# MB1166.net
KiCad netlist of a schematic drawn in Altium Designer
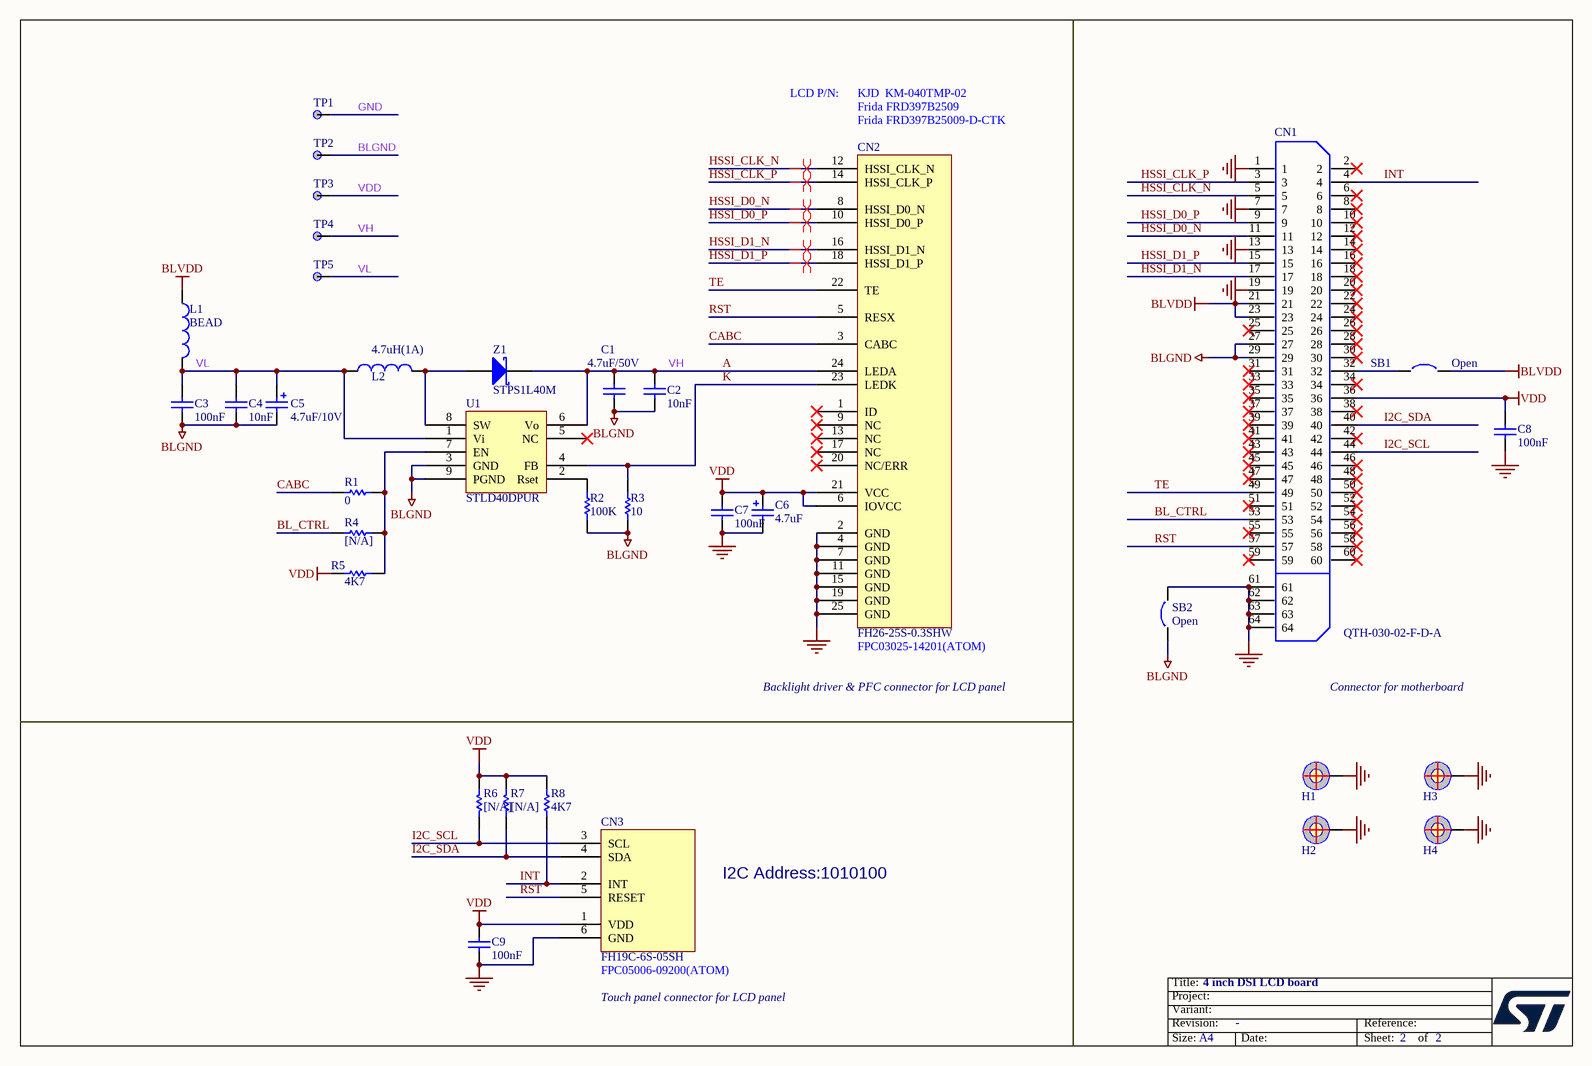
[diagram p0: MB1166.SchDoc]

(export (version "E")
  (design (tool "Eeschema 10.0.6"))
  (components
    (comp (ref "C1")
      (value "4.7uF/50V")
      (footprint "1206C")
      (description "Capacitor")
      (fields (field (name "PUBLISHER") "Altium Limited"))
      (libsource (lib "Miscellaneous Devices") (part "CAP"))
    )
    (comp (ref "C2")
      (value "10nF")
      (footprint "0603C")
      (description "Capacitor")
      (fields (field (name "PUBLISHER") "Altium Limited"))
      (libsource (lib "*") (part "CAP"))
    )
    (comp (ref "C3")
      (value "100nF")
      (footprint "0603C")
      (description "Capacitor")
      (fields (field (name "PUBLISHER") "Altium Limited"))
      (libsource (lib "Miscellaneous Devices") (part "CAP"))
    )
    (comp (ref "C4")
      (value "10nF")
      (footprint "0603C")
      (description "Capacitor")
      (fields (field (name "PUBLISHER") "Altium Limited"))
      (libsource (lib "Miscellaneous Devices") (part "CAP"))
    )
    (comp (ref "C5")
      (value "4.7uF/10V")
      (footprint "1206C")
      (description "Polarized Capacitor (Radial)")
      (fields (field (name "PUBLISHER") "Altium Limited"))
      (libsource (lib "Miscellaneous Devices") (part "Cap Pol1"))
    )
    (comp (ref "C6")
      (value "4.7uF")
      (footprint "TAN-A")
      (description "Polarized Capacitor (Radial)")
      (fields (field (name "PUBLISHER") "Altium Limited"))
      (libsource (lib "Miscellaneous Devices") (part "Cap Pol1"))
    )
    (comp (ref "C7")
      (value "100nF")
      (footprint "0603C")
      (description "Capacitor")
      (fields (field (name "PUBLISHER") "Altium Limited"))
      (libsource (lib "Miscellaneous Devices") (part "CAP"))
    )
    (comp (ref "C8")
      (value "100nF")
      (footprint "0603C")
      (description "Capacitor")
      (fields (field (name "PUBLISHER") "Altium Limited"))
      (libsource (lib "Miscellaneous Devices") (part "CAP"))
    )
    (comp (ref "C9")
      (value "100nF")
      (footprint "0603C")
      (description "Capacitor")
      (fields (field (name "PUBLISHER") "Altium Limited"))
      (libsource (lib "Miscellaneous Devices") (part "CAP"))
    )
    (comp (ref "CN1")
      (value "QTH-030-02-F-D-A")
      (footprint "QTH-030-02-F-D-A")
      (description "HIGH SPEED TERMINAL STRIP, .5mm PITCH, 60 PINS.")
      (fields (field (name "MANUFACTURER") "SAMTEC") (field (name "CREATED") "16 FEB 2013 - WENDY XIN"))
      (libsource (lib "MB1165") (part "QTH-030-02-F-D-A"))
    )
    (comp (ref "CN2")
      (value "FH26-25S-0.3SHW")
      (footprint "FPC25_FPC03025-1420")
      (libsource (lib "MB1166") (part "FH26-25S-0.3SHW"))
    )
    (comp (ref "CN3")
      (value "FH19C-6S-05SH")
      (footprint "FH19C-6S-0R5Sh_FPC_CPT")
      (libsource (lib "MB1166") (part "FH19C-6S-05SH"))
    )
    (comp (ref "H1")
      (value "POSITION HOLE")
      (footprint "HOLE_C9D4R5")
      (libsource (lib "mb1045") (part "POSITION HOLE"))
    )
    (comp (ref "H2")
      (value "POSITION HOLE")
      (footprint "HOLE_C9D4R5")
      (libsource (lib "mb1045") (part "POSITION HOLE"))
    )
    (comp (ref "H3")
      (value "POSITION HOLE")
      (footprint "HOLE_C9D4R5")
      (libsource (lib "mb1045") (part "POSITION HOLE"))
    )
    (comp (ref "H4")
      (value "POSITION HOLE")
      (footprint "HOLE_C9D4R5")
      (libsource (lib "mb1045") (part "POSITION HOLE"))
    )
    (comp (ref "L1")
      (value "BEAD")
      (footprint "0603L")
      (description "Inductor")
      (fields (field (name "PUBLISHER") "Altium Limited"))
      (libsource (lib "Miscellaneous Devices") (part "Inductor"))
    )
    (comp (ref "L2")
      (value "4.7uH(1A)")
      (footprint "1210L")
      (description "Inductor")
      (fields (field (name "PUBLISHER") "Altium Limited"))
      (libsource (lib "Miscellaneous Devices") (part "Inductor"))
    )
    (comp (ref "R1")
      (value "0")
      (footprint "0603R")
      (description "Resistor")
      (fields (field (name "PUBLISHER") "Altium Limited"))
      (libsource (lib "Miscellaneous Devices") (part "Res1"))
    )
    (comp (ref "R2")
      (value "100K")
      (footprint "0603R")
      (description "Resistor")
      (fields (field (name "PUBLISHER") "Altium Limited"))
      (libsource (lib "Miscellaneous Devices") (part "Res1"))
    )
    (comp (ref "R3")
      (value "10")
      (footprint "0603R")
      (description "Resistor")
      (fields (field (name "PUBLISHER") "Altium Limited"))
      (libsource (lib "Miscellaneous Devices") (part "Res1"))
    )
    (comp (ref "R4")
      (value "[N/A]")
      (footprint "0603R")
      (description "Resistor")
      (fields (field (name "PUBLISHER") "Altium Limited"))
      (libsource (lib "Miscellaneous Devices") (part "Res1"))
    )
    (comp (ref "R5")
      (value "4K7")
      (footprint "0603R")
      (description "Resistor")
      (fields (field (name "PUBLISHER") "Altium Limited"))
      (libsource (lib "Miscellaneous Devices") (part "Res1"))
    )
    (comp (ref "R6")
      (value "[N/A]")
      (footprint "0603R")
      (description "Resistor")
      (fields (field (name "PUBLISHER") "Altium Limited"))
      (libsource (lib "*") (part "Res1"))
    )
    (comp (ref "R7")
      (value "[N/A]")
      (footprint "0603R")
      (description "Resistor")
      (fields (field (name "PUBLISHER") "Altium Limited"))
      (libsource (lib "*") (part "Res1"))
    )
    (comp (ref "R8")
      (value "4K7")
      (footprint "0603R")
      (description "Resistor")
      (fields (field (name "PUBLISHER") "Altium Limited"))
      (libsource (lib "*") (part "Res1"))
    )
    (comp (ref "SB1")
      (value "Open")
      (footprint "SB_0603")
      (description "Circuit Breaker")
      (fields (field (name "PUBLISHER") "Altium Limited"))
      (libsource (lib "MB1165") (part "Circuit Breaker"))
    )
    (comp (ref "SB2")
      (value "Open")
      (footprint "SB_0603")
      (description "Circuit Breaker")
      (fields (field (name "PUBLISHER") "Altium Limited"))
      (libsource (lib "MB1165") (part "Circuit Breaker"))
    )
    (comp (ref "TP1") (value "~") (footprint "TP") (libsource (lib "*") (part "TP")))
    (comp (ref "TP2") (value "~") (footprint "TP") (libsource (lib "*") (part "TP")))
    (comp (ref "TP3") (value "~") (footprint "TP") (libsource (lib "*") (part "TP")))
    (comp (ref "TP4") (value "~") (footprint "TP") (libsource (lib "*") (part "TP")))
    (comp (ref "TP5") (value "~") (footprint "TP") (libsource (lib "*") (part "TP")))
    (comp (ref "U1")
      (value "STLD40DPUR")
      (footprint "SON8_0R65_3X3")
      (libsource (lib "3.2LCD_daughterboard") (part "STLD40DPMR"))
    )
    (comp (ref "Z1")
      (value "STPS1L40M")
      (footprint "DO-216AA")
      (description "Schottky Diode")
      (fields (field (name "PUBLISHER") "Altium Limited"))
      (libsource (lib "Miscellaneous Devices") (part "D Schottky"))
    )
  )
  (nets
    (net (code "1") (name "/A") (class "Default")
      (node (ref "C1") (pin "1") (pinfunction "1_1") (pintype "passive"))
      (node (ref "C2") (pin "2") (pinfunction "2_2") (pintype "passive"))
      (node (ref "CN2") (pin "24") (pinfunction "LEDA_24") (pintype "passive"))
      (node (ref "TP4") (pin "1") (pinfunction "1_1") (pintype "passive"))
      (node (ref "U1") (pin "6") (pinfunction "Vo_6") (pintype "passive"))
      (node (ref "Z1") (pin "2") (pinfunction "K_2") (pintype "passive"))
    )
    (net (code "2") (name "/BL_CTRL") (class "Default")
      (node (ref "CN1") (pin "53") (pinfunction "53_53") (pintype "passive"))
      (node (ref "R4") (pin "2") (pinfunction "2_2") (pintype "passive"))
    )
    (net (code "3") (name "/CABC") (class "Default")
      (node (ref "CN2") (pin "3") (pinfunction "CABC_3") (pintype "passive"))
      (node (ref "R1") (pin "2") (pinfunction "2_2") (pintype "passive"))
    )
    (net (code "4") (name "/HSSI_CLK_N") (class "Default")
      (node (ref "CN1") (pin "5") (pinfunction "5_5") (pintype "passive"))
      (node (ref "CN2") (pin "12") (pinfunction "HSSI_CLK_N_12") (pintype "passive"))
    )
    (net (code "5") (name "/HSSI_CLK_P") (class "Default")
      (node (ref "CN1") (pin "3") (pinfunction "3_3") (pintype "passive"))
      (node (ref "CN2") (pin "14") (pinfunction "HSSI_CLK_P_14") (pintype "passive"))
    )
    (net (code "6") (name "/HSSI_D0_N") (class "Default")
      (node (ref "CN1") (pin "11") (pinfunction "11_11") (pintype "passive"))
      (node (ref "CN2") (pin "8") (pinfunction "HSSI_D0_N_8") (pintype "passive"))
    )
    (net (code "7") (name "/HSSI_D0_P") (class "Default")
      (node (ref "CN1") (pin "9") (pinfunction "9_9") (pintype "passive"))
      (node (ref "CN2") (pin "10") (pinfunction "HSSI_D0_P_10") (pintype "passive"))
    )
    (net (code "8") (name "/HSSI_D1_N") (class "Default")
      (node (ref "CN1") (pin "17") (pinfunction "17_17") (pintype "passive"))
      (node (ref "CN2") (pin "16") (pinfunction "HSSI_D1_N_16") (pintype "passive"))
    )
    (net (code "9") (name "/HSSI_D1_P") (class "Default")
      (node (ref "CN1") (pin "15") (pinfunction "15_15") (pintype "passive"))
      (node (ref "CN2") (pin "18") (pinfunction "HSSI_D1_P_18") (pintype "passive"))
    )
    (net (code "10") (name "/I2C_SCL") (class "Default")
      (node (ref "CN1") (pin "44") (pinfunction "44_44") (pintype "passive"))
      (node (ref "CN3") (pin "3") (pinfunction "SCL_3") (pintype "passive"))
      (node (ref "R6") (pin "1") (pinfunction "1_1") (pintype "passive"))
    )
    (net (code "11") (name "/I2C_SDA") (class "Default")
      (node (ref "CN1") (pin "40") (pinfunction "40_40") (pintype "passive"))
      (node (ref "CN3") (pin "4") (pinfunction "SDA_4") (pintype "passive"))
      (node (ref "R7") (pin "1") (pinfunction "1_1") (pintype "passive"))
    )
    (net (code "12") (name "/INT") (class "Default")
      (node (ref "CN1") (pin "4") (pinfunction "4_4") (pintype "passive"))
      (node (ref "CN3") (pin "2") (pinfunction "INT_2") (pintype "passive"))
      (node (ref "R8") (pin "2") (pinfunction "2_2") (pintype "passive"))
    )
    (net (code "13") (name "/K") (class "Default")
      (node (ref "CN2") (pin "23") (pinfunction "LEDK_23") (pintype "passive"))
      (node (ref "R3") (pin "2") (pinfunction "2_2") (pintype "passive"))
      (node (ref "U1") (pin "4") (pinfunction "FB_4") (pintype "passive"))
    )
    (net (code "14") (name "/RST") (class "Default")
      (node (ref "CN1") (pin "57") (pinfunction "57_57") (pintype "passive"))
      (node (ref "CN2") (pin "5") (pinfunction "RESX_5") (pintype "passive"))
      (node (ref "CN3") (pin "5") (pinfunction "RESET_5") (pintype "passive"))
    )
    (net (code "15") (name "/TE") (class "Default")
      (node (ref "CN1") (pin "49") (pinfunction "49_49") (pintype "passive"))
      (node (ref "CN2") (pin "22") (pinfunction "TE_22") (pintype "passive"))
    )
    (net (code "16") (name "/VL") (class "Default")
      (node (ref "C3") (pin "2") (pinfunction "2_2") (pintype "passive"))
      (node (ref "C4") (pin "2") (pinfunction "2_2") (pintype "passive"))
      (node (ref "C5") (pin "1") (pinfunction "1_1") (pintype "passive"))
      (node (ref "L1") (pin "2") (pinfunction "2_2") (pintype "passive"))
      (node (ref "L2") (pin "1") (pinfunction "1_1") (pintype "passive"))
      (node (ref "TP5") (pin "1") (pinfunction "1_1") (pintype "passive"))
      (node (ref "U1") (pin "1") (pinfunction "Vi_1") (pintype "passive"))
    )
    (net (code "17") (name "BLGND") (class "Default")
      (node (ref "C1") (pin "2") (pinfunction "2_2") (pintype "passive"))
      (node (ref "C2") (pin "1") (pinfunction "1_1") (pintype "passive"))
      (node (ref "C3") (pin "1") (pinfunction "1_1") (pintype "passive"))
      (node (ref "C4") (pin "1") (pinfunction "1_1") (pintype "passive"))
      (node (ref "C5") (pin "2") (pinfunction "2_2") (pintype "passive"))
      (node (ref "CN1") (pin "27") (pinfunction "27_27") (pintype "passive"))
      (node (ref "CN1") (pin "29") (pinfunction "29_29") (pintype "passive"))
      (node (ref "R2") (pin "2") (pinfunction "2_2") (pintype "passive"))
      (node (ref "R3") (pin "1") (pinfunction "1_1") (pintype "passive"))
      (node (ref "SB2") (pin "1") (pinfunction "1_1") (pintype "passive"))
      (node (ref "TP2") (pin "1") (pinfunction "1_1") (pintype "passive"))
      (node (ref "U1") (pin "3") (pinfunction "GND_3") (pintype "passive"))
      (node (ref "U1") (pin "9") (pinfunction "PGND_9") (pintype "passive"))
    )
    (net (code "18") (name "BLVDD") (class "Default")
      (node (ref "CN1") (pin "21") (pinfunction "21_21") (pintype "passive"))
      (node (ref "CN1") (pin "23") (pinfunction "23_23") (pintype "passive"))
      (node (ref "L1") (pin "1") (pinfunction "1_1") (pintype "passive"))
      (node (ref "SB1") (pin "2") (pinfunction "2_2") (pintype "passive"))
    )
    (net (code "19") (name "GND") (class "Default")
      (node (ref "C6") (pin "2") (pinfunction "2_2") (pintype "passive"))
      (node (ref "C7") (pin "1") (pinfunction "1_1") (pintype "passive"))
      (node (ref "C8") (pin "1") (pinfunction "1_1") (pintype "passive"))
      (node (ref "C9") (pin "1") (pinfunction "1_1") (pintype "passive"))
      (node (ref "CN1") (pin "1") (pinfunction "1_1") (pintype "passive"))
      (node (ref "CN1") (pin "13") (pinfunction "13_13") (pintype "passive"))
      (node (ref "CN1") (pin "19") (pinfunction "19_19") (pintype "passive"))
      (node (ref "CN1") (pin "61") (pinfunction "61_61") (pintype "passive"))
      (node (ref "CN1") (pin "62") (pinfunction "62_62") (pintype "passive"))
      (node (ref "CN1") (pin "63") (pinfunction "63_63") (pintype "passive"))
      (node (ref "CN1") (pin "64") (pinfunction "64_64") (pintype "passive"))
      (node (ref "CN1") (pin "7") (pinfunction "7_7") (pintype "passive"))
      (node (ref "CN2") (pin "11") (pinfunction "GND_11") (pintype "passive"))
      (node (ref "CN2") (pin "15") (pinfunction "GND_15") (pintype "passive"))
      (node (ref "CN2") (pin "19") (pinfunction "GND_19") (pintype "passive"))
      (node (ref "CN2") (pin "2") (pinfunction "GND_2") (pintype "passive"))
      (node (ref "CN2") (pin "25") (pinfunction "GND_25") (pintype "passive"))
      (node (ref "CN2") (pin "4") (pinfunction "GND_4") (pintype "passive"))
      (node (ref "CN2") (pin "7") (pinfunction "GND_7") (pintype "passive"))
      (node (ref "CN3") (pin "6") (pinfunction "GND_6") (pintype "passive"))
      (node (ref "H1") (pin "1") (pinfunction "1_1") (pintype "passive"))
      (node (ref "H2") (pin "1") (pinfunction "1_1") (pintype "passive"))
      (node (ref "H3") (pin "1") (pinfunction "1_1") (pintype "passive"))
      (node (ref "H4") (pin "1") (pinfunction "1_1") (pintype "passive"))
      (node (ref "SB2") (pin "2") (pinfunction "2_2") (pintype "passive"))
      (node (ref "TP1") (pin "1") (pinfunction "1_1") (pintype "passive"))
    )
    (net (code "20") (name "Net-(CN1-Pad32)") (class "Default")
      (node (ref "CN1") (pin "32") (pinfunction "32_32") (pintype "passive"))
      (node (ref "SB1") (pin "1") (pinfunction "1_1") (pintype "passive"))
    )
    (net (code "21") (name "Net-(U1-EN)") (class "Default")
      (node (ref "R1") (pin "1") (pinfunction "1_1") (pintype "passive"))
      (node (ref "R4") (pin "1") (pinfunction "1_1") (pintype "passive"))
      (node (ref "R5") (pin "1") (pinfunction "1_1") (pintype "passive"))
      (node (ref "U1") (pin "7") (pinfunction "EN_7") (pintype "passive"))
    )
    (net (code "22") (name "Net-(U1-Rset)") (class "Default")
      (node (ref "R2") (pin "1") (pinfunction "1_1") (pintype "passive"))
      (node (ref "U1") (pin "2") (pinfunction "Rset_2") (pintype "passive"))
    )
    (net (code "23") (name "Net-(U1-SW)") (class "Default")
      (node (ref "L2") (pin "2") (pinfunction "2_2") (pintype "passive"))
      (node (ref "U1") (pin "8") (pinfunction "SW_8") (pintype "passive"))
      (node (ref "Z1") (pin "1") (pinfunction "A_1") (pintype "passive"))
    )
    (net (code "24") (name "VDD") (class "Default")
      (node (ref "C6") (pin "1") (pinfunction "1_1") (pintype "passive"))
      (node (ref "C7") (pin "2") (pinfunction "2_2") (pintype "passive"))
      (node (ref "C8") (pin "2") (pinfunction "2_2") (pintype "passive"))
      (node (ref "C9") (pin "2") (pinfunction "2_2") (pintype "passive"))
      (node (ref "CN1") (pin "36") (pinfunction "36_36") (pintype "passive"))
      (node (ref "CN2") (pin "21") (pinfunction "VCC_21") (pintype "passive"))
      (node (ref "CN2") (pin "6") (pinfunction "IOVCC_6") (pintype "passive"))
      (node (ref "CN3") (pin "1") (pinfunction "VDD_1") (pintype "passive"))
      (node (ref "R5") (pin "2") (pinfunction "2_2") (pintype "passive"))
      (node (ref "R6") (pin "2") (pinfunction "2_2") (pintype "passive"))
      (node (ref "R7") (pin "2") (pinfunction "2_2") (pintype "passive"))
      (node (ref "R8") (pin "1") (pinfunction "1_1") (pintype "passive"))
      (node (ref "TP3") (pin "1") (pinfunction "1_1") (pintype "passive"))
    )
    (net (code "25") (name "unconnected-(CN1-Pad2)") (class "Default")
      (node (ref "CN1") (pin "2") (pinfunction "2_2") (pintype "passive+no_connect"))
    )
    (net (code "26") (name "unconnected-(CN1-Pad6)") (class "Default")
      (node (ref "CN1") (pin "6") (pinfunction "6_6") (pintype "passive+no_connect"))
    )
    (net (code "27") (name "unconnected-(CN1-Pad8)") (class "Default")
      (node (ref "CN1") (pin "8") (pinfunction "8_8") (pintype "passive+no_connect"))
    )
    (net (code "28") (name "unconnected-(CN1-Pad10)") (class "Default")
      (node (ref "CN1") (pin "10") (pinfunction "10_10") (pintype "passive+no_connect"))
    )
    (net (code "29") (name "unconnected-(CN1-Pad12)") (class "Default")
      (node (ref "CN1") (pin "12") (pinfunction "12_12") (pintype "passive+no_connect"))
    )
    (net (code "30") (name "unconnected-(CN1-Pad14)") (class "Default")
      (node (ref "CN1") (pin "14") (pinfunction "14_14") (pintype "passive+no_connect"))
    )
    (net (code "31") (name "unconnected-(CN1-Pad16)") (class "Default")
      (node (ref "CN1") (pin "16") (pinfunction "16_16") (pintype "passive+no_connect"))
    )
    (net (code "32") (name "unconnected-(CN1-Pad18)") (class "Default")
      (node (ref "CN1") (pin "18") (pinfunction "18_18") (pintype "passive+no_connect"))
    )
    (net (code "33") (name "unconnected-(CN1-Pad20)") (class "Default")
      (node (ref "CN1") (pin "20") (pinfunction "20_20") (pintype "passive+no_connect"))
    )
    (net (code "34") (name "unconnected-(CN1-Pad22)") (class "Default")
      (node (ref "CN1") (pin "22") (pinfunction "22_22") (pintype "passive+no_connect"))
    )
    (net (code "35") (name "unconnected-(CN1-Pad24)") (class "Default")
      (node (ref "CN1") (pin "24") (pinfunction "24_24") (pintype "passive+no_connect"))
    )
    (net (code "36") (name "unconnected-(CN1-Pad25)") (class "Default")
      (node (ref "CN1") (pin "25") (pinfunction "25_25") (pintype "passive+no_connect"))
    )
    (net (code "37") (name "unconnected-(CN1-Pad26)") (class "Default")
      (node (ref "CN1") (pin "26") (pinfunction "26_26") (pintype "passive+no_connect"))
    )
    (net (code "38") (name "unconnected-(CN1-Pad28)") (class "Default")
      (node (ref "CN1") (pin "28") (pinfunction "28_28") (pintype "passive+no_connect"))
    )
    (net (code "39") (name "unconnected-(CN1-Pad30)") (class "Default")
      (node (ref "CN1") (pin "30") (pinfunction "30_30") (pintype "passive+no_connect"))
    )
    (net (code "40") (name "unconnected-(CN1-Pad31)") (class "Default")
      (node (ref "CN1") (pin "31") (pinfunction "31_31") (pintype "passive+no_connect"))
    )
    (net (code "41") (name "unconnected-(CN1-Pad33)") (class "Default")
      (node (ref "CN1") (pin "33") (pinfunction "33_33") (pintype "passive+no_connect"))
    )
    (net (code "42") (name "unconnected-(CN1-Pad34)") (class "Default")
      (node (ref "CN1") (pin "34") (pinfunction "34_34") (pintype "passive+no_connect"))
    )
    (net (code "43") (name "unconnected-(CN1-Pad35)") (class "Default")
      (node (ref "CN1") (pin "35") (pinfunction "35_35") (pintype "passive+no_connect"))
    )
    (net (code "44") (name "unconnected-(CN1-Pad37)") (class "Default")
      (node (ref "CN1") (pin "37") (pinfunction "37_37") (pintype "passive+no_connect"))
    )
    (net (code "45") (name "unconnected-(CN1-Pad38)") (class "Default")
      (node (ref "CN1") (pin "38") (pinfunction "38_38") (pintype "passive+no_connect"))
    )
    (net (code "46") (name "unconnected-(CN1-Pad39)") (class "Default")
      (node (ref "CN1") (pin "39") (pinfunction "39_39") (pintype "passive+no_connect"))
    )
    (net (code "47") (name "unconnected-(CN1-Pad41)") (class "Default")
      (node (ref "CN1") (pin "41") (pinfunction "41_41") (pintype "passive+no_connect"))
    )
    (net (code "48") (name "unconnected-(CN1-Pad42)") (class "Default")
      (node (ref "CN1") (pin "42") (pinfunction "42_42") (pintype "passive+no_connect"))
    )
    (net (code "49") (name "unconnected-(CN1-Pad43)") (class "Default")
      (node (ref "CN1") (pin "43") (pinfunction "43_43") (pintype "passive+no_connect"))
    )
    (net (code "50") (name "unconnected-(CN1-Pad45)") (class "Default")
      (node (ref "CN1") (pin "45") (pinfunction "45_45") (pintype "passive+no_connect"))
    )
    (net (code "51") (name "unconnected-(CN1-Pad46)") (class "Default")
      (node (ref "CN1") (pin "46") (pinfunction "46_46") (pintype "passive+no_connect"))
    )
    (net (code "52") (name "unconnected-(CN1-Pad47)") (class "Default")
      (node (ref "CN1") (pin "47") (pinfunction "47_47") (pintype "passive+no_connect"))
    )
    (net (code "53") (name "unconnected-(CN1-Pad48)") (class "Default")
      (node (ref "CN1") (pin "48") (pinfunction "48_48") (pintype "passive+no_connect"))
    )
    (net (code "54") (name "unconnected-(CN1-Pad50)") (class "Default")
      (node (ref "CN1") (pin "50") (pinfunction "50_50") (pintype "passive+no_connect"))
    )
    (net (code "55") (name "unconnected-(CN1-Pad51)") (class "Default")
      (node (ref "CN1") (pin "51") (pinfunction "51_51") (pintype "passive+no_connect"))
    )
    (net (code "56") (name "unconnected-(CN1-Pad52)") (class "Default")
      (node (ref "CN1") (pin "52") (pinfunction "52_52") (pintype "passive+no_connect"))
    )
    (net (code "57") (name "unconnected-(CN1-Pad54)") (class "Default")
      (node (ref "CN1") (pin "54") (pinfunction "54_54") (pintype "passive+no_connect"))
    )
    (net (code "58") (name "unconnected-(CN1-Pad55)") (class "Default")
      (node (ref "CN1") (pin "55") (pinfunction "55_55") (pintype "passive+no_connect"))
    )
    (net (code "59") (name "unconnected-(CN1-Pad56)") (class "Default")
      (node (ref "CN1") (pin "56") (pinfunction "56_56") (pintype "passive+no_connect"))
    )
    (net (code "60") (name "unconnected-(CN1-Pad58)") (class "Default")
      (node (ref "CN1") (pin "58") (pinfunction "58_58") (pintype "passive+no_connect"))
    )
    (net (code "61") (name "unconnected-(CN1-Pad59)") (class "Default")
      (node (ref "CN1") (pin "59") (pinfunction "59_59") (pintype "passive+no_connect"))
    )
    (net (code "62") (name "unconnected-(CN1-Pad60)") (class "Default")
      (node (ref "CN1") (pin "60") (pinfunction "60_60") (pintype "passive+no_connect"))
    )
    (net (code "63") (name "unconnected-(CN2-ID-Pad1)") (class "Default")
      (node (ref "CN2") (pin "1") (pinfunction "ID_1") (pintype "passive+no_connect"))
    )
    (net (code "64") (name "unconnected-(CN2-NC-Pad9)") (class "Default")
      (node (ref "CN2") (pin "9") (pinfunction "NC_9") (pintype "passive+no_connect"))
    )
    (net (code "65") (name "unconnected-(CN2-NC-Pad13)") (class "Default")
      (node (ref "CN2") (pin "13") (pinfunction "NC_13") (pintype "passive+no_connect"))
    )
    (net (code "66") (name "unconnected-(CN2-NC-Pad17)") (class "Default")
      (node (ref "CN2") (pin "17") (pinfunction "NC_17") (pintype "passive+no_connect"))
    )
    (net (code "67") (name "unconnected-(CN2-NC{slash}ERR-Pad20)") (class "Default")
      (node (ref "CN2") (pin "20") (pinfunction "NC/ERR_20") (pintype "passive+no_connect"))
    )
    (net (code "68") (name "unconnected-(U1-NC-Pad5)") (class "Default")
      (node (ref "U1") (pin "5") (pinfunction "NC_5") (pintype "passive+no_connect"))
    )
  )
)
